# design.net
KiCad netlist of a schematic drawn in Altium Designer
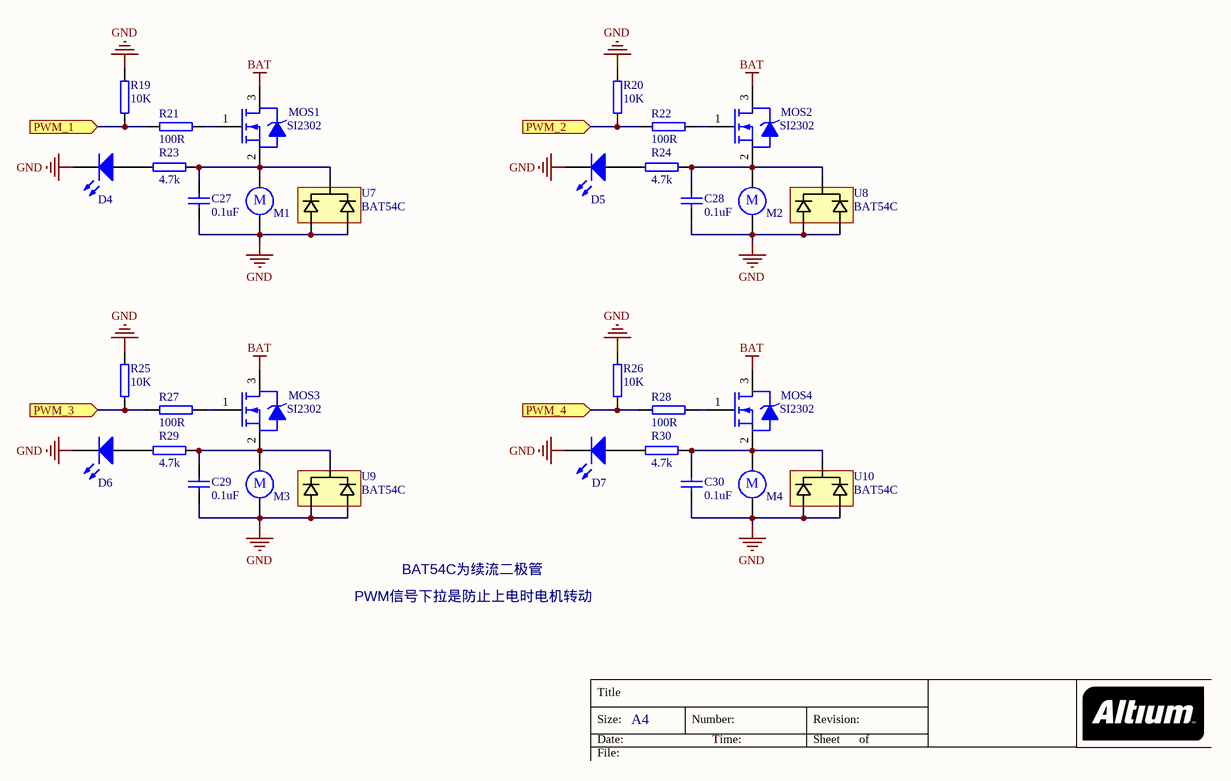
[diagram p0: 驱动.SchDoc]

(export (version "E")
  (design (tool "Eeschema 10.0.6"))
  (components
    (comp (ref "C27") (value "0.1uF") (footprint "CAP-0603") (libsource (lib "Connectors") (part "Cap")))
    (comp (ref "C28") (value "0.1uF") (footprint "CAP-0603") (libsource (lib "Connectors") (part "Cap")))
    (comp (ref "C29") (value "0.1uF") (footprint "CAP-0603") (libsource (lib "Connectors") (part "Cap")))
    (comp (ref "C30") (value "0.1uF") (footprint "CAP-0603") (libsource (lib "Connectors") (part "Cap")))
    (comp (ref "D4") (value "LED") (footprint "LED-BLU-0603") (libsource (lib "Connectors") (part "LED")))
    (comp (ref "D5") (value "LED") (footprint "LED-BLU-0603") (libsource (lib "Connectors") (part "LED")))
    (comp (ref "D6") (value "LED") (footprint "LED-BLU-0603") (libsource (lib "Connectors") (part "LED")))
    (comp (ref "D7") (value "LED") (footprint "LED-BLU-0603") (libsource (lib "Connectors") (part "LED")))
    (comp (ref "M1")
      (value "Motor")
      (footprint "Header-2.0-SMD")
      (fields (field (name "PUBLISHER") "Altium Limited"))
      (libsource (lib "Connectors") (part "Motor"))
    )
    (comp (ref "M2")
      (value "Motor")
      (footprint "Header-2.0-SMD")
      (fields (field (name "PUBLISHER") "Altium Limited"))
      (libsource (lib "Connectors") (part "Motor"))
    )
    (comp (ref "M3")
      (value "Motor")
      (footprint "Header-2.0-SMD")
      (fields (field (name "PUBLISHER") "Altium Limited"))
      (libsource (lib "Connectors") (part "Motor"))
    )
    (comp (ref "M4")
      (value "Motor")
      (footprint "Header-2.0-SMD")
      (fields (field (name "PUBLISHER") "Altium Limited"))
      (libsource (lib "Connectors") (part "Motor"))
    )
    (comp (ref "MOS1") (value "SI2302") (footprint "SOT-23-3-L") (libsource (lib "Devices") (part "N-MOS")))
    (comp (ref "MOS2") (value "SI2302") (footprint "SOT-23-3-L") (libsource (lib "Devices") (part "N-MOS")))
    (comp (ref "MOS3") (value "SI2302") (footprint "SOT-23-3-L") (libsource (lib "Devices") (part "N-MOS")))
    (comp (ref "MOS4") (value "SI2302") (footprint "SOT-23-3-L") (libsource (lib "Devices") (part "N-MOS")))
    (comp (ref "R19") (value "10K") (footprint "RES-0603") (libsource (lib "Connectors") (part "Res")))
    (comp (ref "R20") (value "10K") (footprint "RES-0603") (libsource (lib "Connectors") (part "Res")))
    (comp (ref "R21") (value "100R") (footprint "RES-0603") (libsource (lib "Connectors") (part "Res")))
    (comp (ref "R22") (value "100R") (footprint "RES-0603") (libsource (lib "Connectors") (part "Res")))
    (comp (ref "R23") (value "4.7k") (footprint "RES-0603") (libsource (lib "Connectors") (part "Res")))
    (comp (ref "R24") (value "4.7k") (footprint "RES-0603") (libsource (lib "Connectors") (part "Res")))
    (comp (ref "R25") (value "10K") (footprint "RES-0603") (libsource (lib "Connectors") (part "Res")))
    (comp (ref "R26") (value "10K") (footprint "RES-0603") (libsource (lib "Connectors") (part "Res")))
    (comp (ref "R27") (value "100R") (footprint "RES-0603") (libsource (lib "Connectors") (part "Res")))
    (comp (ref "R28") (value "100R") (footprint "RES-0603") (libsource (lib "Connectors") (part "Res")))
    (comp (ref "R29") (value "4.7k") (footprint "RES-0603") (libsource (lib "Connectors") (part "Res")))
    (comp (ref "R30") (value "4.7k") (footprint "RES-0603") (libsource (lib "Connectors") (part "Res")))
    (comp (ref "U7") (value "BAT54C") (footprint "SOT-23-3-L") (libsource (lib "Devices") (part "BAT54C")))
    (comp (ref "U8") (value "BAT54C") (footprint "SOT-23-3-L") (libsource (lib "Devices") (part "BAT54C")))
    (comp (ref "U9") (value "BAT54C") (footprint "SOT-23-3-L") (libsource (lib "Devices") (part "BAT54C")))
    (comp (ref "U10") (value "BAT54C") (footprint "SOT-23-3-L") (libsource (lib "Devices") (part "BAT54C")))
  )
  (nets
    (net (code "1") (name "/PWM_1") (class "Default")
      (node (ref "R19") (pin "2") (pinfunction "2_2") (pintype "passive"))
      (node (ref "R21") (pin "1") (pinfunction "1_1") (pintype "passive"))
    )
    (net (code "2") (name "/PWM_2") (class "Default")
      (node (ref "R20") (pin "2") (pinfunction "2_2") (pintype "passive"))
      (node (ref "R22") (pin "1") (pinfunction "1_1") (pintype "passive"))
    )
    (net (code "3") (name "/PWM_3") (class "Default")
      (node (ref "R25") (pin "2") (pinfunction "2_2") (pintype "passive"))
      (node (ref "R27") (pin "1") (pinfunction "1_1") (pintype "passive"))
    )
    (net (code "4") (name "/PWM_4") (class "Default")
      (node (ref "R26") (pin "2") (pinfunction "2_2") (pintype "passive"))
      (node (ref "R28") (pin "1") (pinfunction "1_1") (pintype "passive"))
    )
    (net (code "5") (name "BAT") (class "Default")
      (node (ref "MOS1") (pin "3") (pinfunction "D_3") (pintype "passive"))
      (node (ref "MOS2") (pin "3") (pinfunction "D_3") (pintype "passive"))
      (node (ref "MOS3") (pin "3") (pinfunction "D_3") (pintype "passive"))
      (node (ref "MOS4") (pin "3") (pinfunction "D_3") (pintype "passive"))
    )
    (net (code "6") (name "GND") (class "Default")
      (node (ref "C27") (pin "2") (pinfunction "2_2") (pintype "passive"))
      (node (ref "C28") (pin "2") (pinfunction "2_2") (pintype "passive"))
      (node (ref "C29") (pin "2") (pinfunction "2_2") (pintype "passive"))
      (node (ref "C30") (pin "2") (pinfunction "2_2") (pintype "passive"))
      (node (ref "D4") (pin "K") (pinfunction "2_K") (pintype "passive"))
      (node (ref "D5") (pin "K") (pinfunction "2_K") (pintype "passive"))
      (node (ref "D6") (pin "K") (pinfunction "2_K") (pintype "passive"))
      (node (ref "D7") (pin "K") (pinfunction "2_K") (pintype "passive"))
      (node (ref "M1") (pin "2") (pinfunction "2_2") (pintype "passive"))
      (node (ref "M2") (pin "2") (pinfunction "2_2") (pintype "passive"))
      (node (ref "M3") (pin "2") (pinfunction "2_2") (pintype "passive"))
      (node (ref "M4") (pin "2") (pinfunction "2_2") (pintype "passive"))
      (node (ref "R19") (pin "1") (pinfunction "1_1") (pintype "passive"))
      (node (ref "R20") (pin "1") (pinfunction "1_1") (pintype "passive"))
      (node (ref "R25") (pin "1") (pinfunction "1_1") (pintype "passive"))
      (node (ref "R26") (pin "1") (pinfunction "1_1") (pintype "passive"))
      (node (ref "U10") (pin "1") (pinfunction "1_1") (pintype "passive"))
      (node (ref "U10") (pin "2") (pinfunction "2_2") (pintype "passive"))
      (node (ref "U7") (pin "1") (pinfunction "1_1") (pintype "passive"))
      (node (ref "U7") (pin "2") (pinfunction "2_2") (pintype "passive"))
      (node (ref "U8") (pin "1") (pinfunction "1_1") (pintype "passive"))
      (node (ref "U8") (pin "2") (pinfunction "2_2") (pintype "passive"))
      (node (ref "U9") (pin "1") (pinfunction "1_1") (pintype "passive"))
      (node (ref "U9") (pin "2") (pinfunction "2_2") (pintype "passive"))
    )
    (net (code "7") (name "Net-(D4-1)") (class "Default")
      (node (ref "D4") (pin "A") (pinfunction "1_A") (pintype "passive"))
      (node (ref "R23") (pin "1") (pinfunction "1_1") (pintype "passive"))
    )
    (net (code "8") (name "Net-(D5-1)") (class "Default")
      (node (ref "D5") (pin "A") (pinfunction "1_A") (pintype "passive"))
      (node (ref "R24") (pin "1") (pinfunction "1_1") (pintype "passive"))
    )
    (net (code "9") (name "Net-(D6-1)") (class "Default")
      (node (ref "D6") (pin "A") (pinfunction "1_A") (pintype "passive"))
      (node (ref "R29") (pin "1") (pinfunction "1_1") (pintype "passive"))
    )
    (net (code "10") (name "Net-(D7-1)") (class "Default")
      (node (ref "D7") (pin "A") (pinfunction "1_A") (pintype "passive"))
      (node (ref "R30") (pin "1") (pinfunction "1_1") (pintype "passive"))
    )
    (net (code "11") (name "Net-(MOS1-G)") (class "Default")
      (node (ref "MOS1") (pin "1") (pinfunction "G_1") (pintype "passive"))
      (node (ref "R21") (pin "2") (pinfunction "2_2") (pintype "passive"))
    )
    (net (code "12") (name "Net-(MOS1-S)") (class "Default")
      (node (ref "C27") (pin "1") (pinfunction "1_1") (pintype "passive"))
      (node (ref "M1") (pin "1") (pinfunction "1_1") (pintype "passive"))
      (node (ref "MOS1") (pin "2") (pinfunction "S_2") (pintype "passive"))
      (node (ref "R23") (pin "2") (pinfunction "2_2") (pintype "passive"))
      (node (ref "U7") (pin "3") (pinfunction "3_3") (pintype "passive"))
    )
    (net (code "13") (name "Net-(MOS2-G)") (class "Default")
      (node (ref "MOS2") (pin "1") (pinfunction "G_1") (pintype "passive"))
      (node (ref "R22") (pin "2") (pinfunction "2_2") (pintype "passive"))
    )
    (net (code "14") (name "Net-(MOS2-S)") (class "Default")
      (node (ref "C28") (pin "1") (pinfunction "1_1") (pintype "passive"))
      (node (ref "M2") (pin "1") (pinfunction "1_1") (pintype "passive"))
      (node (ref "MOS2") (pin "2") (pinfunction "S_2") (pintype "passive"))
      (node (ref "R24") (pin "2") (pinfunction "2_2") (pintype "passive"))
      (node (ref "U8") (pin "3") (pinfunction "3_3") (pintype "passive"))
    )
    (net (code "15") (name "Net-(MOS3-G)") (class "Default")
      (node (ref "MOS3") (pin "1") (pinfunction "G_1") (pintype "passive"))
      (node (ref "R27") (pin "2") (pinfunction "2_2") (pintype "passive"))
    )
    (net (code "16") (name "Net-(MOS3-S)") (class "Default")
      (node (ref "C29") (pin "1") (pinfunction "1_1") (pintype "passive"))
      (node (ref "M3") (pin "1") (pinfunction "1_1") (pintype "passive"))
      (node (ref "MOS3") (pin "2") (pinfunction "S_2") (pintype "passive"))
      (node (ref "R29") (pin "2") (pinfunction "2_2") (pintype "passive"))
      (node (ref "U9") (pin "3") (pinfunction "3_3") (pintype "passive"))
    )
    (net (code "17") (name "Net-(MOS4-G)") (class "Default")
      (node (ref "MOS4") (pin "1") (pinfunction "G_1") (pintype "passive"))
      (node (ref "R28") (pin "2") (pinfunction "2_2") (pintype "passive"))
    )
    (net (code "18") (name "Net-(MOS4-S)") (class "Default")
      (node (ref "C30") (pin "1") (pinfunction "1_1") (pintype "passive"))
      (node (ref "M4") (pin "1") (pinfunction "1_1") (pintype "passive"))
      (node (ref "MOS4") (pin "2") (pinfunction "S_2") (pintype "passive"))
      (node (ref "R30") (pin "2") (pinfunction "2_2") (pintype "passive"))
      (node (ref "U10") (pin "3") (pinfunction "3_3") (pintype "passive"))
    )
  )
)
